# eeprom_programmer.net
KiCad netlist of a schematic drawn in EAGLE
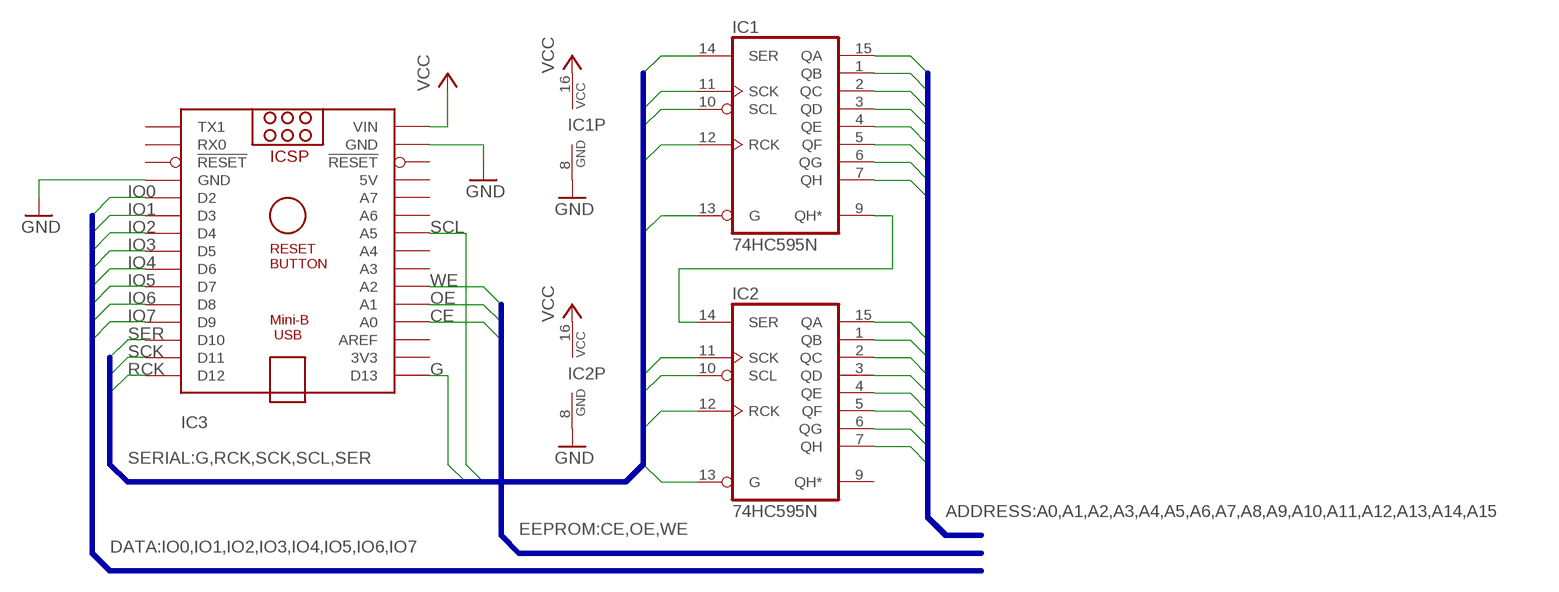
[diagram p0: schematic, sheet 1]

(export (version "E")
  (design (tool "Eeschema 10.0.6"))
  (components
    (comp (ref "IC1")
      (value "74HC595N")
      (footprint "eagle-import:DIL16")
      (libsource (lib "eagle-import") (part "74595NHC"))
    )
    (comp (ref "IC2")
      (value "74HC595N")
      (footprint "eagle-import:DIL16")
      (libsource (lib "eagle-import") (part "74595NHC"))
    )
    (comp (ref "IC3")
      (value "ARDUINO-NANO")
      (footprint "eagle-import:ARDUINO_NANO")
      (libsource (lib "eagle-import") (part "ARDUINO-NANO"))
    )
  )
  (nets
    (net (code "20") (name "/5V") (class "Default")
      (node (ref "IC3") (pin "12") (pinfunction "5V_12") (pintype "power_in"))
    )
    (net (code "21") (name "/CE") (class "Default")
      (node (ref "IC3") (pin "4") (pinfunction "A0_4") (pintype "bidirectional"))
    )
    (net (code "22") (name "/G") (class "Default")
      (node (ref "IC1") (pin "13") (pinfunction "G_13") (pintype "input"))
      (node (ref "IC2") (pin "13") (pinfunction "G_13") (pintype "input"))
      (node (ref "IC3") (pin "1") (pinfunction "D13_1") (pintype "bidirectional"))
    )
    (net (code "23") (name "/IO0") (class "Default")
      (node (ref "IC3") (pin "20") (pinfunction "D2_20") (pintype "bidirectional"))
    )
    (net (code "24") (name "/IO1") (class "Default")
      (node (ref "IC3") (pin "21") (pinfunction "D3_21") (pintype "bidirectional"))
    )
    (net (code "25") (name "/IO2") (class "Default")
      (node (ref "IC3") (pin "22") (pinfunction "D4_22") (pintype "bidirectional"))
    )
    (net (code "26") (name "/IO3") (class "Default")
      (node (ref "IC3") (pin "23") (pinfunction "D5_23") (pintype "bidirectional"))
    )
    (net (code "27") (name "/IO4") (class "Default")
      (node (ref "IC3") (pin "24") (pinfunction "D6_24") (pintype "bidirectional"))
    )
    (net (code "28") (name "/IO5") (class "Default")
      (node (ref "IC3") (pin "25") (pinfunction "D7_25") (pintype "bidirectional"))
    )
    (net (code "29") (name "/IO6") (class "Default")
      (node (ref "IC3") (pin "26") (pinfunction "D8_26") (pintype "bidirectional"))
    )
    (net (code "30") (name "/IO7") (class "Default")
      (node (ref "IC3") (pin "27") (pinfunction "D9_27") (pintype "bidirectional"))
    )
    (net (code "31") (name "/OE") (class "Default")
      (node (ref "IC3") (pin "5") (pinfunction "A1_5") (pintype "bidirectional"))
    )
    (net (code "32") (name "/RCK") (class "Default")
      (node (ref "IC1") (pin "12") (pinfunction "RCK_12") (pintype "input"))
      (node (ref "IC2") (pin "12") (pinfunction "RCK_12") (pintype "input"))
      (node (ref "IC3") (pin "30") (pinfunction "D12_30") (pintype "bidirectional"))
    )
    (net (code "33") (name "/SCK") (class "Default")
      (node (ref "IC1") (pin "11") (pinfunction "SCK_11") (pintype "input"))
      (node (ref "IC2") (pin "11") (pinfunction "SCK_11") (pintype "input"))
      (node (ref "IC3") (pin "29") (pinfunction "D11_29") (pintype "bidirectional"))
    )
    (net (code "34") (name "/SCL") (class "Default")
      (node (ref "IC1") (pin "10") (pinfunction "SCL_10") (pintype "input"))
      (node (ref "IC2") (pin "10") (pinfunction "SCL_10") (pintype "input"))
      (node (ref "IC3") (pin "9") (pinfunction "A5_9") (pintype "bidirectional"))
    )
    (net (code "35") (name "/SER") (class "Default")
      (node (ref "IC1") (pin "14") (pinfunction "SER_14") (pintype "input"))
      (node (ref "IC3") (pin "28") (pinfunction "D10_28") (pintype "bidirectional"))
    )
    (net (code "36") (name "/WE") (class "Default")
      (node (ref "IC3") (pin "6") (pinfunction "A2_6") (pintype "bidirectional"))
    )
    (net (code "41") (name "GND") (class "Default")
      (node (ref "IC1") (pin "8") (pinfunction "GND_8") (pintype "power_in"))
      (node (ref "IC2") (pin "8") (pinfunction "GND_8") (pintype "power_in"))
      (node (ref "IC3") (pin "14") (pinfunction "GND_14") (pintype "power_in"))
      (node (ref "IC3") (pin "19") (pinfunction "GND_19") (pintype "power_in"))
    )
    (net (code "42") (name "Net-(IC1A-QH*)") (class "Default")
      (node (ref "IC1") (pin "9") (pinfunction "QH*_9") (pintype "tri_state"))
      (node (ref "IC2") (pin "14") (pinfunction "SER_14") (pintype "input"))
    )
    (net (code "43") (name "VCC") (class "Default")
      (node (ref "IC1") (pin "16") (pinfunction "VCC_16") (pintype "power_in"))
      (node (ref "IC2") (pin "16") (pinfunction "VCC_16") (pintype "power_in"))
      (node (ref "IC3") (pin "15") (pinfunction "VIN_15") (pintype "power_in"))
    )
    (net (code "44") (name "unconnected-(IC1A-QA-Pad15)") (class "Default")
      (node (ref "IC1") (pin "15") (pinfunction "QA_15") (pintype "tri_state"))
    )
    (net (code "45") (name "unconnected-(IC1A-QB-Pad1)") (class "Default")
      (node (ref "IC1") (pin "1") (pinfunction "QB_1") (pintype "tri_state"))
    )
    (net (code "46") (name "unconnected-(IC1A-QC-Pad2)") (class "Default")
      (node (ref "IC1") (pin "2") (pinfunction "QC_2") (pintype "tri_state"))
    )
    (net (code "47") (name "unconnected-(IC1A-QD-Pad3)") (class "Default")
      (node (ref "IC1") (pin "3") (pinfunction "QD_3") (pintype "tri_state"))
    )
    (net (code "48") (name "unconnected-(IC1A-QE-Pad4)") (class "Default")
      (node (ref "IC1") (pin "4") (pinfunction "QE_4") (pintype "tri_state"))
    )
    (net (code "49") (name "unconnected-(IC1A-QF-Pad5)") (class "Default")
      (node (ref "IC1") (pin "5") (pinfunction "QF_5") (pintype "tri_state"))
    )
    (net (code "50") (name "unconnected-(IC1A-QG-Pad6)") (class "Default")
      (node (ref "IC1") (pin "6") (pinfunction "QG_6") (pintype "tri_state"))
    )
    (net (code "51") (name "unconnected-(IC1A-QH-Pad7)") (class "Default")
      (node (ref "IC1") (pin "7") (pinfunction "QH_7") (pintype "tri_state"))
    )
    (net (code "52") (name "unconnected-(IC2A-QA-Pad15)") (class "Default")
      (node (ref "IC2") (pin "15") (pinfunction "QA_15") (pintype "tri_state"))
    )
    (net (code "53") (name "unconnected-(IC2A-QB-Pad1)") (class "Default")
      (node (ref "IC2") (pin "1") (pinfunction "QB_1") (pintype "tri_state"))
    )
    (net (code "54") (name "unconnected-(IC2A-QC-Pad2)") (class "Default")
      (node (ref "IC2") (pin "2") (pinfunction "QC_2") (pintype "tri_state"))
    )
    (net (code "55") (name "unconnected-(IC2A-QD-Pad3)") (class "Default")
      (node (ref "IC2") (pin "3") (pinfunction "QD_3") (pintype "tri_state"))
    )
    (net (code "56") (name "unconnected-(IC2A-QE-Pad4)") (class "Default")
      (node (ref "IC2") (pin "4") (pinfunction "QE_4") (pintype "tri_state"))
    )
    (net (code "57") (name "unconnected-(IC2A-QF-Pad5)") (class "Default")
      (node (ref "IC2") (pin "5") (pinfunction "QF_5") (pintype "tri_state"))
    )
    (net (code "58") (name "unconnected-(IC2A-QG-Pad6)") (class "Default")
      (node (ref "IC2") (pin "6") (pinfunction "QG_6") (pintype "tri_state"))
    )
    (net (code "59") (name "unconnected-(IC2A-QH*-Pad9)") (class "Default")
      (node (ref "IC2") (pin "9") (pinfunction "QH*_9") (pintype "tri_state"))
    )
    (net (code "60") (name "unconnected-(IC2A-QH-Pad7)") (class "Default")
      (node (ref "IC2") (pin "7") (pinfunction "QH_7") (pintype "tri_state"))
    )
    (net (code "61") (name "unconnected-(IC3-3V3-Pad2)") (class "Default")
      (node (ref "IC3") (pin "2") (pinfunction "3V3_2") (pintype "output"))
    )
    (net (code "62") (name "unconnected-(IC3-A3-Pad7)") (class "Default")
      (node (ref "IC3") (pin "7") (pinfunction "A3_7") (pintype "bidirectional"))
    )
    (net (code "63") (name "unconnected-(IC3-A4-Pad8)") (class "Default")
      (node (ref "IC3") (pin "8") (pinfunction "A4_8") (pintype "bidirectional"))
    )
    (net (code "64") (name "unconnected-(IC3-A6-Pad10)") (class "Default")
      (node (ref "IC3") (pin "10") (pinfunction "A6_10") (pintype "bidirectional"))
    )
    (net (code "65") (name "unconnected-(IC3-A7-Pad11)") (class "Default")
      (node (ref "IC3") (pin "11") (pinfunction "A7_11") (pintype "bidirectional"))
    )
    (net (code "66") (name "unconnected-(IC3-AREF-Pad3)") (class "Default")
      (node (ref "IC3") (pin "3") (pinfunction "AREF_3") (pintype "input"))
    )
    (net (code "67") (name "unconnected-(IC3-RX0-Pad17)") (class "Default")
      (node (ref "IC3") (pin "17") (pinfunction "RX0_17") (pintype "bidirectional"))
    )
    (net (code "68") (name "unconnected-(IC3-TX1-Pad16)") (class "Default")
      (node (ref "IC3") (pin "16") (pinfunction "TX1_16") (pintype "bidirectional"))
    )
    (net (code "69") (name "unconnected-(IC3-~{RESET}-Pad13)") (class "Default")
      (node (ref "IC3") (pin "13") (pinfunction "~{RESET}_13") (pintype "input"))
    )
    (net (code "70") (name "unconnected-(IC3-~{RESET}-Pad18)") (class "Default")
      (node (ref "IC3") (pin "18") (pinfunction "~{RESET}_18") (pintype "input"))
    )
  )
)
